# ECL_balanced_pulser.net
KiCad netlist of a schematic drawn in EAGLE
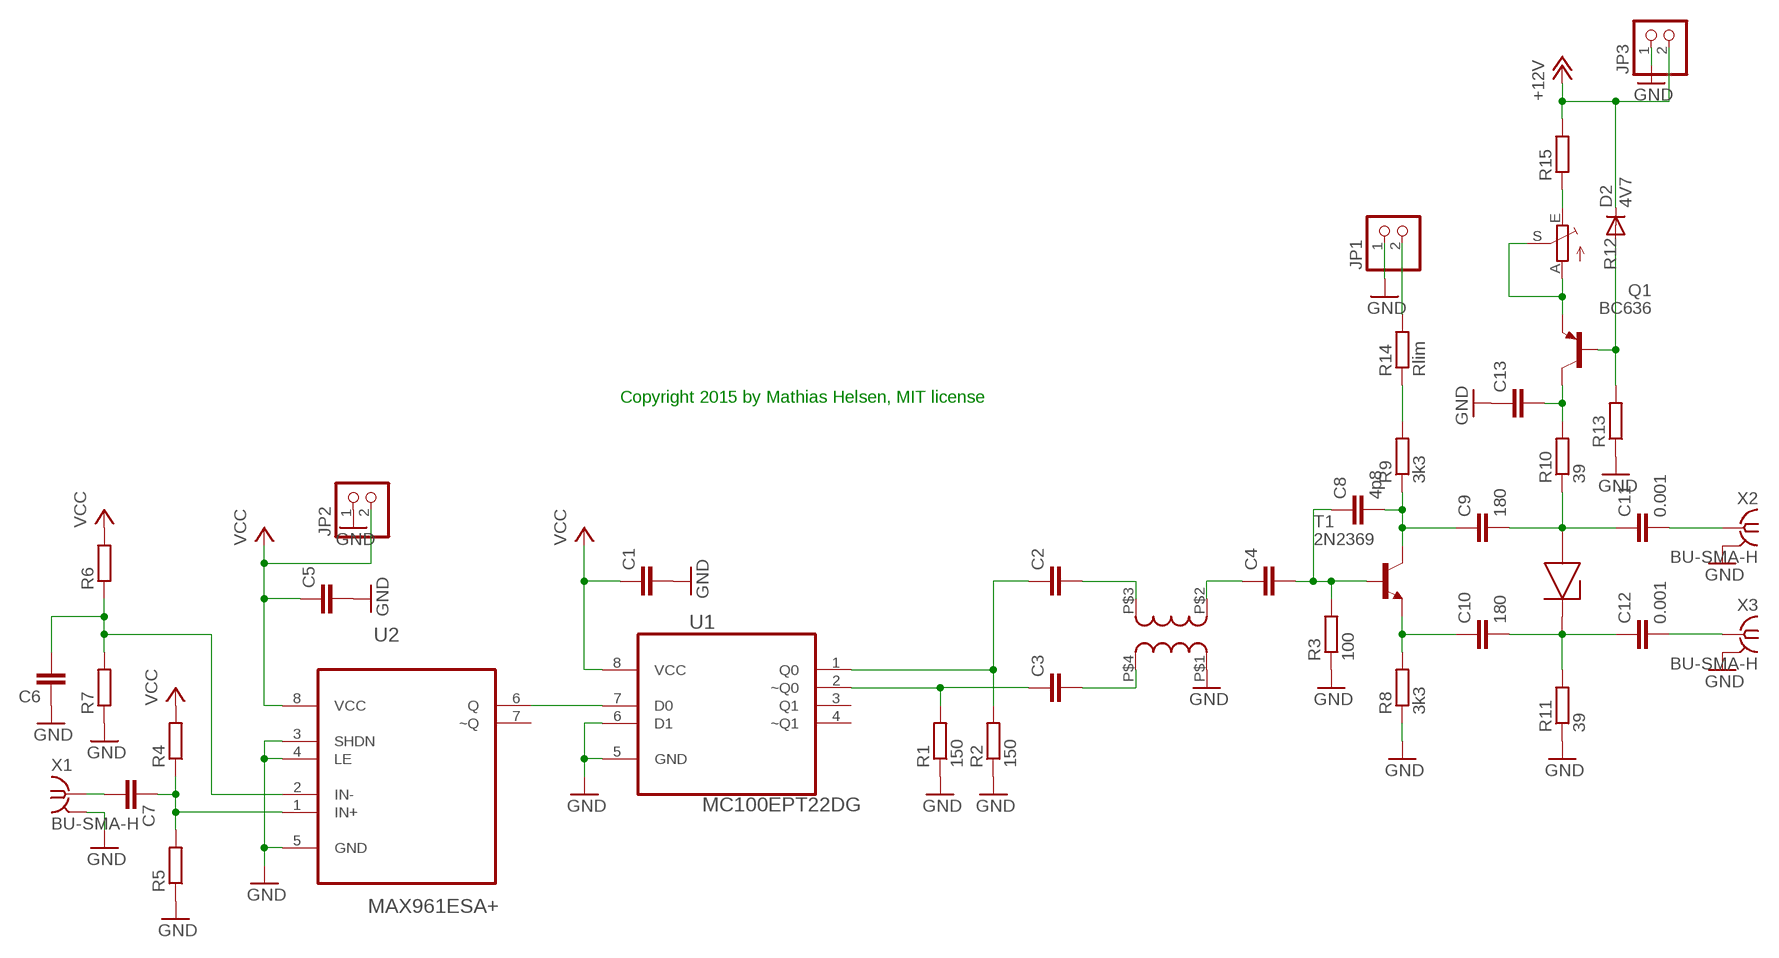
[diagram p0: schematic, sheet 1]

(export (version "E")
  (design (tool "Eeschema 10.0.6"))
  (components
    (comp (ref "C1")
      (value "C-EUC0805")
      (footprint "eagle-import:C0805")
      (libsource (lib "eagle-import") (part "C-EUC0805"))
    )
    (comp (ref "C2")
      (value "C-EUC0805")
      (footprint "eagle-import:C0805")
      (libsource (lib "eagle-import") (part "C-EUC0805"))
    )
    (comp (ref "C3")
      (value "C-EUC0805")
      (footprint "eagle-import:C0805")
      (libsource (lib "eagle-import") (part "C-EUC0805"))
    )
    (comp (ref "C4")
      (value "C-EUC0805")
      (footprint "eagle-import:C0805")
      (libsource (lib "eagle-import") (part "C-EUC0805"))
    )
    (comp (ref "C5")
      (value "C-EUC0805")
      (footprint "eagle-import:C0805")
      (libsource (lib "eagle-import") (part "C-EUC0805"))
    )
    (comp (ref "C6")
      (value "C-EUC0805")
      (footprint "eagle-import:C0805")
      (libsource (lib "eagle-import") (part "C-EUC0805"))
    )
    (comp (ref "C7")
      (value "C-EUC0805")
      (footprint "eagle-import:C0805")
      (libsource (lib "eagle-import") (part "C-EUC0805"))
    )
    (comp (ref "C8")
      (value "4p8")
      (footprint "eagle-import:C0805")
      (libsource (lib "eagle-import") (part "C-EUC0805"))
    )
    (comp (ref "C9")
      (value "180")
      (footprint "eagle-import:C0805")
      (libsource (lib "eagle-import") (part "C-EUC0805"))
    )
    (comp (ref "C10")
      (value "180")
      (footprint "eagle-import:C0805")
      (libsource (lib "eagle-import") (part "C-EUC0805"))
    )
    (comp (ref "C11")
      (value "0.001")
      (footprint "eagle-import:C0805")
      (libsource (lib "eagle-import") (part "C-EUC0805"))
    )
    (comp (ref "C12")
      (value "0.001")
      (footprint "eagle-import:C0805")
      (libsource (lib "eagle-import") (part "C-EUC0805"))
    )
    (comp (ref "C13")
      (value "C-EUC0805")
      (footprint "eagle-import:C0805")
      (libsource (lib "eagle-import") (part "C-EUC0805"))
    )
    (comp (ref "D2")
      (value "4V7")
      (footprint "eagle-import:DO35-7")
      (libsource (lib "eagle-import") (part "1N4148DO35-7"))
    )
    (comp (ref "JP1")
      (value "PINHD-1X2")
      (footprint "eagle-import:1X02")
      (libsource (lib "eagle-import") (part "PINHD-1X2"))
    )
    (comp (ref "JP2")
      (value "PINHD-1X2")
      (footprint "eagle-import:1X02")
      (libsource (lib "eagle-import") (part "PINHD-1X2"))
    )
    (comp (ref "JP3")
      (value "PINHD-1X2")
      (footprint "eagle-import:1X02")
      (libsource (lib "eagle-import") (part "PINHD-1X2"))
    )
    (comp (ref "Q1")
      (value "BC636")
      (footprint "eagle-import:TO92-BCE")
      (libsource (lib "eagle-import") (part "BC636"))
    )
    (comp (ref "R1")
      (value "150")
      (footprint "eagle-import:R0805")
      (libsource (lib "eagle-import") (part "R-EU_R0805"))
    )
    (comp (ref "R2")
      (value "150")
      (footprint "eagle-import:R0805")
      (libsource (lib "eagle-import") (part "R-EU_R0805"))
    )
    (comp (ref "R3")
      (value "100")
      (footprint "eagle-import:R0805")
      (libsource (lib "eagle-import") (part "R-EU_R0805"))
    )
    (comp (ref "R4")
      (value "R-EU_M0805")
      (footprint "eagle-import:M0805")
      (libsource (lib "eagle-import") (part "R-EU_M0805"))
    )
    (comp (ref "R5")
      (value "R-EU_M0805")
      (footprint "eagle-import:M0805")
      (libsource (lib "eagle-import") (part "R-EU_M0805"))
    )
    (comp (ref "R6")
      (value "R-EU_M0805")
      (footprint "eagle-import:M0805")
      (libsource (lib "eagle-import") (part "R-EU_M0805"))
    )
    (comp (ref "R7")
      (value "R-EU_M0805")
      (footprint "eagle-import:M0805")
      (libsource (lib "eagle-import") (part "R-EU_M0805"))
    )
    (comp (ref "R8")
      (value "3k3")
      (footprint "eagle-import:R0805")
      (libsource (lib "eagle-import") (part "R-EU_R0805"))
    )
    (comp (ref "R9")
      (value "3k3")
      (footprint "eagle-import:R0805")
      (libsource (lib "eagle-import") (part "R-EU_R0805"))
    )
    (comp (ref "R10")
      (value "39")
      (footprint "eagle-import:R0805")
      (libsource (lib "eagle-import") (part "R-EU_R0805"))
    )
    (comp (ref "R11")
      (value "39")
      (footprint "eagle-import:R0805")
      (libsource (lib "eagle-import") (part "R-EU_R0805"))
    )
    (comp (ref "R12")
      (value "TRIM_EU-SP19L")
      (footprint "eagle-import:SP19L")
      (libsource (lib "eagle-import") (part "TRIM_EU-SP19L"))
    )
    (comp (ref "R13")
      (value "R-EU_R0805")
      (footprint "eagle-import:R0805")
      (libsource (lib "eagle-import") (part "R-EU_R0805"))
    )
    (comp (ref "R14")
      (value "Rlim")
      (footprint "eagle-import:R0805")
      (libsource (lib "eagle-import") (part "R-EU_R0805"))
    )
    (comp (ref "R15")
      (value "R-EU_R0805")
      (footprint "eagle-import:R0805")
      (libsource (lib "eagle-import") (part "R-EU_R0805"))
    )
    (comp (ref "T1")
      (value "2N2369")
      (footprint "eagle-import:TO18")
      (libsource (lib "eagle-import") (part "2N2369"))
    )
    (comp (ref "U$1")
      (value "JA4220")
      (footprint "eagle-import:T")
      (libsource (lib "eagle-import") (part "JA4220"))
    )
    (comp (ref "U$2")
      (value "2D524A")
      (footprint "eagle-import:2D524A")
      (libsource (lib "eagle-import") (part "2D524A"))
    )
    (comp (ref "U1")
      (value "MC100EPT22DG")
      (footprint "eagle-import:SOIC127P600X175-8N")
      (libsource (lib "eagle-import") (part "MC100EPT22DG"))
    )
    (comp (ref "U2")
      (value "MAX961ESA+")
      (footprint "eagle-import:SOIC127P600X175-8N")
      (libsource (lib "eagle-import") (part "MAX961ESA+"))
    )
    (comp (ref "X1")
      (value "BU-SMA-H")
      (footprint "eagle-import:BU-SMA-H")
      (libsource (lib "eagle-import") (part "BU-SMA-H"))
    )
    (comp (ref "X2")
      (value "BU-SMA-H")
      (footprint "eagle-import:BU-SMA-H")
      (libsource (lib "eagle-import") (part "BU-SMA-H"))
    )
    (comp (ref "X3")
      (value "BU-SMA-H")
      (footprint "eagle-import:BU-SMA-H")
      (libsource (lib "eagle-import") (part "BU-SMA-H"))
    )
  )
  (nets
    (net (code "1") (name "+12V") (class "Default")
      (node (ref "D2") (pin "C") (pinfunction "C_C") (pintype "passive"))
      (node (ref "JP3") (pin "2") (pinfunction "2_2") (pintype "passive"))
      (node (ref "R15") (pin "2") (pinfunction "2_2") (pintype "passive"))
    )
    (net (code "2") (name "GND") (class "Default")
      (node (ref "C1") (pin "2") (pinfunction "2_2") (pintype "passive"))
      (node (ref "C13") (pin "1") (pinfunction "1_1") (pintype "passive"))
      (node (ref "C5") (pin "2") (pinfunction "2_2") (pintype "passive"))
      (node (ref "C6") (pin "1") (pinfunction "1_1") (pintype "passive"))
      (node (ref "JP1") (pin "1") (pinfunction "1_1") (pintype "passive"))
      (node (ref "JP2") (pin "1") (pinfunction "1_1") (pintype "passive"))
      (node (ref "JP3") (pin "1") (pinfunction "1_1") (pintype "passive"))
      (node (ref "R1") (pin "1") (pinfunction "1_1") (pintype "passive"))
      (node (ref "R11") (pin "1") (pinfunction "1_1") (pintype "passive"))
      (node (ref "R13") (pin "1") (pinfunction "1_1") (pintype "passive"))
      (node (ref "R2") (pin "1") (pinfunction "1_1") (pintype "passive"))
      (node (ref "R3") (pin "1") (pinfunction "1_1") (pintype "passive"))
      (node (ref "R5") (pin "1") (pinfunction "1_1") (pintype "passive"))
      (node (ref "R7") (pin "1") (pinfunction "1_1") (pintype "passive"))
      (node (ref "R8") (pin "1") (pinfunction "1_1") (pintype "passive"))
      (node (ref "U$1") (pin "P$1") (pinfunction "P$1_P$1") (pintype "bidirectional"))
      (node (ref "U1") (pin "5") (pinfunction "GND_5") (pintype "passive"))
      (node (ref "U1") (pin "6") (pinfunction "D1_6") (pintype "input"))
      (node (ref "U2") (pin "3") (pinfunction "SHDN_3") (pintype "input"))
      (node (ref "U2") (pin "4") (pinfunction "LE_4") (pintype "input"))
      (node (ref "U2") (pin "5") (pinfunction "GND_5") (pintype "passive"))
      (node (ref "X1") (pin "2") (pinfunction "2_2") (pintype "passive"))
      (node (ref "X1") (pin "3") (pinfunction "2_3") (pintype "passive"))
      (node (ref "X1") (pin "4") (pinfunction "2_4") (pintype "passive"))
      (node (ref "X1") (pin "5") (pinfunction "2_5") (pintype "passive"))
      (node (ref "X2") (pin "2") (pinfunction "2_2") (pintype "passive"))
      (node (ref "X2") (pin "3") (pinfunction "2_3") (pintype "passive"))
      (node (ref "X2") (pin "4") (pinfunction "2_4") (pintype "passive"))
      (node (ref "X2") (pin "5") (pinfunction "2_5") (pintype "passive"))
      (node (ref "X3") (pin "2") (pinfunction "2_2") (pintype "passive"))
      (node (ref "X3") (pin "3") (pinfunction "2_3") (pintype "passive"))
      (node (ref "X3") (pin "4") (pinfunction "2_4") (pintype "passive"))
      (node (ref "X3") (pin "5") (pinfunction "2_5") (pintype "passive"))
    )
    (net (code "3") (name "Net-(C2-Pad2)") (class "Default")
      (node (ref "C2") (pin "2") (pinfunction "2_2") (pintype "passive"))
      (node (ref "U$1") (pin "P$3") (pinfunction "P$3_P$3") (pintype "bidirectional"))
    )
    (net (code "4") (name "Net-(C3-Pad2)") (class "Default")
      (node (ref "C3") (pin "2") (pinfunction "2_2") (pintype "passive"))
      (node (ref "U$1") (pin "P$4") (pinfunction "P$4_P$4") (pintype "bidirectional"))
    )
    (net (code "5") (name "Net-(C4-Pad1)") (class "Default")
      (node (ref "C4") (pin "1") (pinfunction "1_1") (pintype "passive"))
      (node (ref "U$1") (pin "P$2") (pinfunction "P$2_P$2") (pintype "bidirectional"))
    )
    (net (code "6") (name "Net-(C7-Pad2)") (class "Default")
      (node (ref "C7") (pin "2") (pinfunction "2_2") (pintype "passive"))
      (node (ref "X1") (pin "1") (pinfunction "1_1") (pintype "passive"))
    )
    (net (code "7") (name "Net-(C10-Pad2)") (class "Default")
      (node (ref "C10") (pin "2") (pinfunction "2_2") (pintype "passive"))
      (node (ref "C12") (pin "1") (pinfunction "1_1") (pintype "passive"))
      (node (ref "R11") (pin "2") (pinfunction "2_2") (pintype "passive"))
      (node (ref "U$2") (pin "CATHODE") (pinfunction "CATHODE_CATHODE") (pintype "bidirectional"))
    )
    (net (code "8") (name "Net-(C11-Pad1)") (class "Default")
      (node (ref "C11") (pin "1") (pinfunction "1_1") (pintype "passive"))
      (node (ref "C9") (pin "2") (pinfunction "2_2") (pintype "passive"))
      (node (ref "R10") (pin "1") (pinfunction "1_1") (pintype "passive"))
      (node (ref "U$2") (pin "ANODE") (pinfunction "ANODE_ANODE") (pintype "bidirectional"))
    )
    (net (code "9") (name "Net-(C11-Pad2)") (class "Default")
      (node (ref "C11") (pin "2") (pinfunction "2_2") (pintype "passive"))
      (node (ref "X2") (pin "1") (pinfunction "1_1") (pintype "passive"))
    )
    (net (code "10") (name "Net-(C12-Pad2)") (class "Default")
      (node (ref "C12") (pin "2") (pinfunction "2_2") (pintype "passive"))
      (node (ref "X3") (pin "1") (pinfunction "1_1") (pintype "passive"))
    )
    (net (code "11") (name "Net-(C13-Pad2)") (class "Default")
      (node (ref "C13") (pin "2") (pinfunction "2_2") (pintype "passive"))
      (node (ref "Q1") (pin "C") (pinfunction "C_C") (pintype "passive"))
      (node (ref "R10") (pin "2") (pinfunction "2_2") (pintype "passive"))
    )
    (net (code "12") (name "Net-(D2-PadA)") (class "Default")
      (node (ref "D2") (pin "A") (pinfunction "A_A") (pintype "passive"))
      (node (ref "Q1") (pin "B") (pinfunction "B_B") (pintype "passive"))
      (node (ref "R13") (pin "2") (pinfunction "2_2") (pintype "passive"))
    )
    (net (code "13") (name "Net-(JP1-Pad2)") (class "Default")
      (node (ref "JP1") (pin "2") (pinfunction "2_2") (pintype "passive"))
      (node (ref "R14") (pin "2") (pinfunction "2_2") (pintype "passive"))
    )
    (net (code "14") (name "Net-(Q1-PadE)") (class "Default")
      (node (ref "Q1") (pin "E") (pinfunction "E_E") (pintype "passive"))
      (node (ref "R12") (pin "A") (pinfunction "A_A") (pintype "passive"))
      (node (ref "R12") (pin "S") (pinfunction "S_S") (pintype "passive"))
    )
    (net (code "15") (name "Net-(R12-PadE)") (class "Default")
      (node (ref "R12") (pin "E") (pinfunction "E_E") (pintype "passive"))
      (node (ref "R15") (pin "1") (pinfunction "1_1") (pintype "passive"))
    )
    (net (code "16") (name "Net-(R14-Pad1)") (class "Default")
      (node (ref "R14") (pin "1") (pinfunction "1_1") (pintype "passive"))
      (node (ref "R9") (pin "2") (pinfunction "2_2") (pintype "passive"))
    )
    (net (code "17") (name "Net-(T1-B)") (class "Default")
      (node (ref "C4") (pin "2") (pinfunction "2_2") (pintype "passive"))
      (node (ref "C8") (pin "1") (pinfunction "1_1") (pintype "passive"))
      (node (ref "R3") (pin "2") (pinfunction "2_2") (pintype "passive"))
      (node (ref "T1") (pin "2") (pinfunction "B_2") (pintype "passive"))
    )
    (net (code "18") (name "Net-(T1-C)") (class "Default")
      (node (ref "C8") (pin "2") (pinfunction "2_2") (pintype "passive"))
      (node (ref "C9") (pin "1") (pinfunction "1_1") (pintype "passive"))
      (node (ref "R9") (pin "1") (pinfunction "1_1") (pintype "passive"))
      (node (ref "T1") (pin "3") (pinfunction "C_3") (pintype "passive"))
    )
    (net (code "19") (name "Net-(T1-E)") (class "Default")
      (node (ref "C10") (pin "1") (pinfunction "1_1") (pintype "passive"))
      (node (ref "R8") (pin "2") (pinfunction "2_2") (pintype "passive"))
      (node (ref "T1") (pin "1") (pinfunction "E_1") (pintype "passive"))
    )
    (net (code "20") (name "Net-(U1-D0)") (class "Default")
      (node (ref "U1") (pin "7") (pinfunction "D0_7") (pintype "input"))
      (node (ref "U2") (pin "6") (pinfunction "Q_6") (pintype "output"))
    )
    (net (code "21") (name "Net-(U1-Q0)") (class "Default")
      (node (ref "C2") (pin "1") (pinfunction "1_1") (pintype "passive"))
      (node (ref "R2") (pin "2") (pinfunction "2_2") (pintype "passive"))
      (node (ref "U1") (pin "1") (pinfunction "Q0_1") (pintype "output"))
    )
    (net (code "22") (name "Net-(U1-~{Q0})") (class "Default")
      (node (ref "C3") (pin "1") (pinfunction "1_1") (pintype "passive"))
      (node (ref "R1") (pin "2") (pinfunction "2_2") (pintype "passive"))
      (node (ref "U1") (pin "2") (pinfunction "~{Q0}_2") (pintype "output"))
    )
    (net (code "23") (name "Net-(U2-IN+)") (class "Default")
      (node (ref "C7") (pin "1") (pinfunction "1_1") (pintype "passive"))
      (node (ref "R4") (pin "1") (pinfunction "1_1") (pintype "passive"))
      (node (ref "R5") (pin "2") (pinfunction "2_2") (pintype "passive"))
      (node (ref "U2") (pin "1") (pinfunction "IN+_1") (pintype "input"))
    )
    (net (code "24") (name "Net-(U2-IN-)") (class "Default")
      (node (ref "C6") (pin "2") (pinfunction "2_2") (pintype "passive"))
      (node (ref "R6") (pin "1") (pinfunction "1_1") (pintype "passive"))
      (node (ref "R7") (pin "2") (pinfunction "2_2") (pintype "passive"))
      (node (ref "U2") (pin "2") (pinfunction "IN-_2") (pintype "input"))
    )
    (net (code "25") (name "VCC") (class "Default")
      (node (ref "C1") (pin "1") (pinfunction "1_1") (pintype "passive"))
      (node (ref "C5") (pin "1") (pinfunction "1_1") (pintype "passive"))
      (node (ref "JP2") (pin "2") (pinfunction "2_2") (pintype "passive"))
      (node (ref "R4") (pin "2") (pinfunction "2_2") (pintype "passive"))
      (node (ref "R6") (pin "2") (pinfunction "2_2") (pintype "passive"))
      (node (ref "U1") (pin "8") (pinfunction "VCC_8") (pintype "power_in"))
      (node (ref "U2") (pin "8") (pinfunction "VCC_8") (pintype "power_in"))
    )
    (net (code "26") (name "unconnected-(U1-Q1-Pad3)") (class "Default")
      (node (ref "U1") (pin "3") (pinfunction "Q1_3") (pintype "output"))
    )
    (net (code "27") (name "unconnected-(U1-~{Q1}-Pad4)") (class "Default")
      (node (ref "U1") (pin "4") (pinfunction "~{Q1}_4") (pintype "output"))
    )
    (net (code "28") (name "unconnected-(U2-~{Q}-Pad7)") (class "Default")
      (node (ref "U2") (pin "7") (pinfunction "~{Q}_7") (pintype "output"))
    )
  )
)
